# Robosapien1.net
KiCad netlist of a schematic drawn in EAGLE
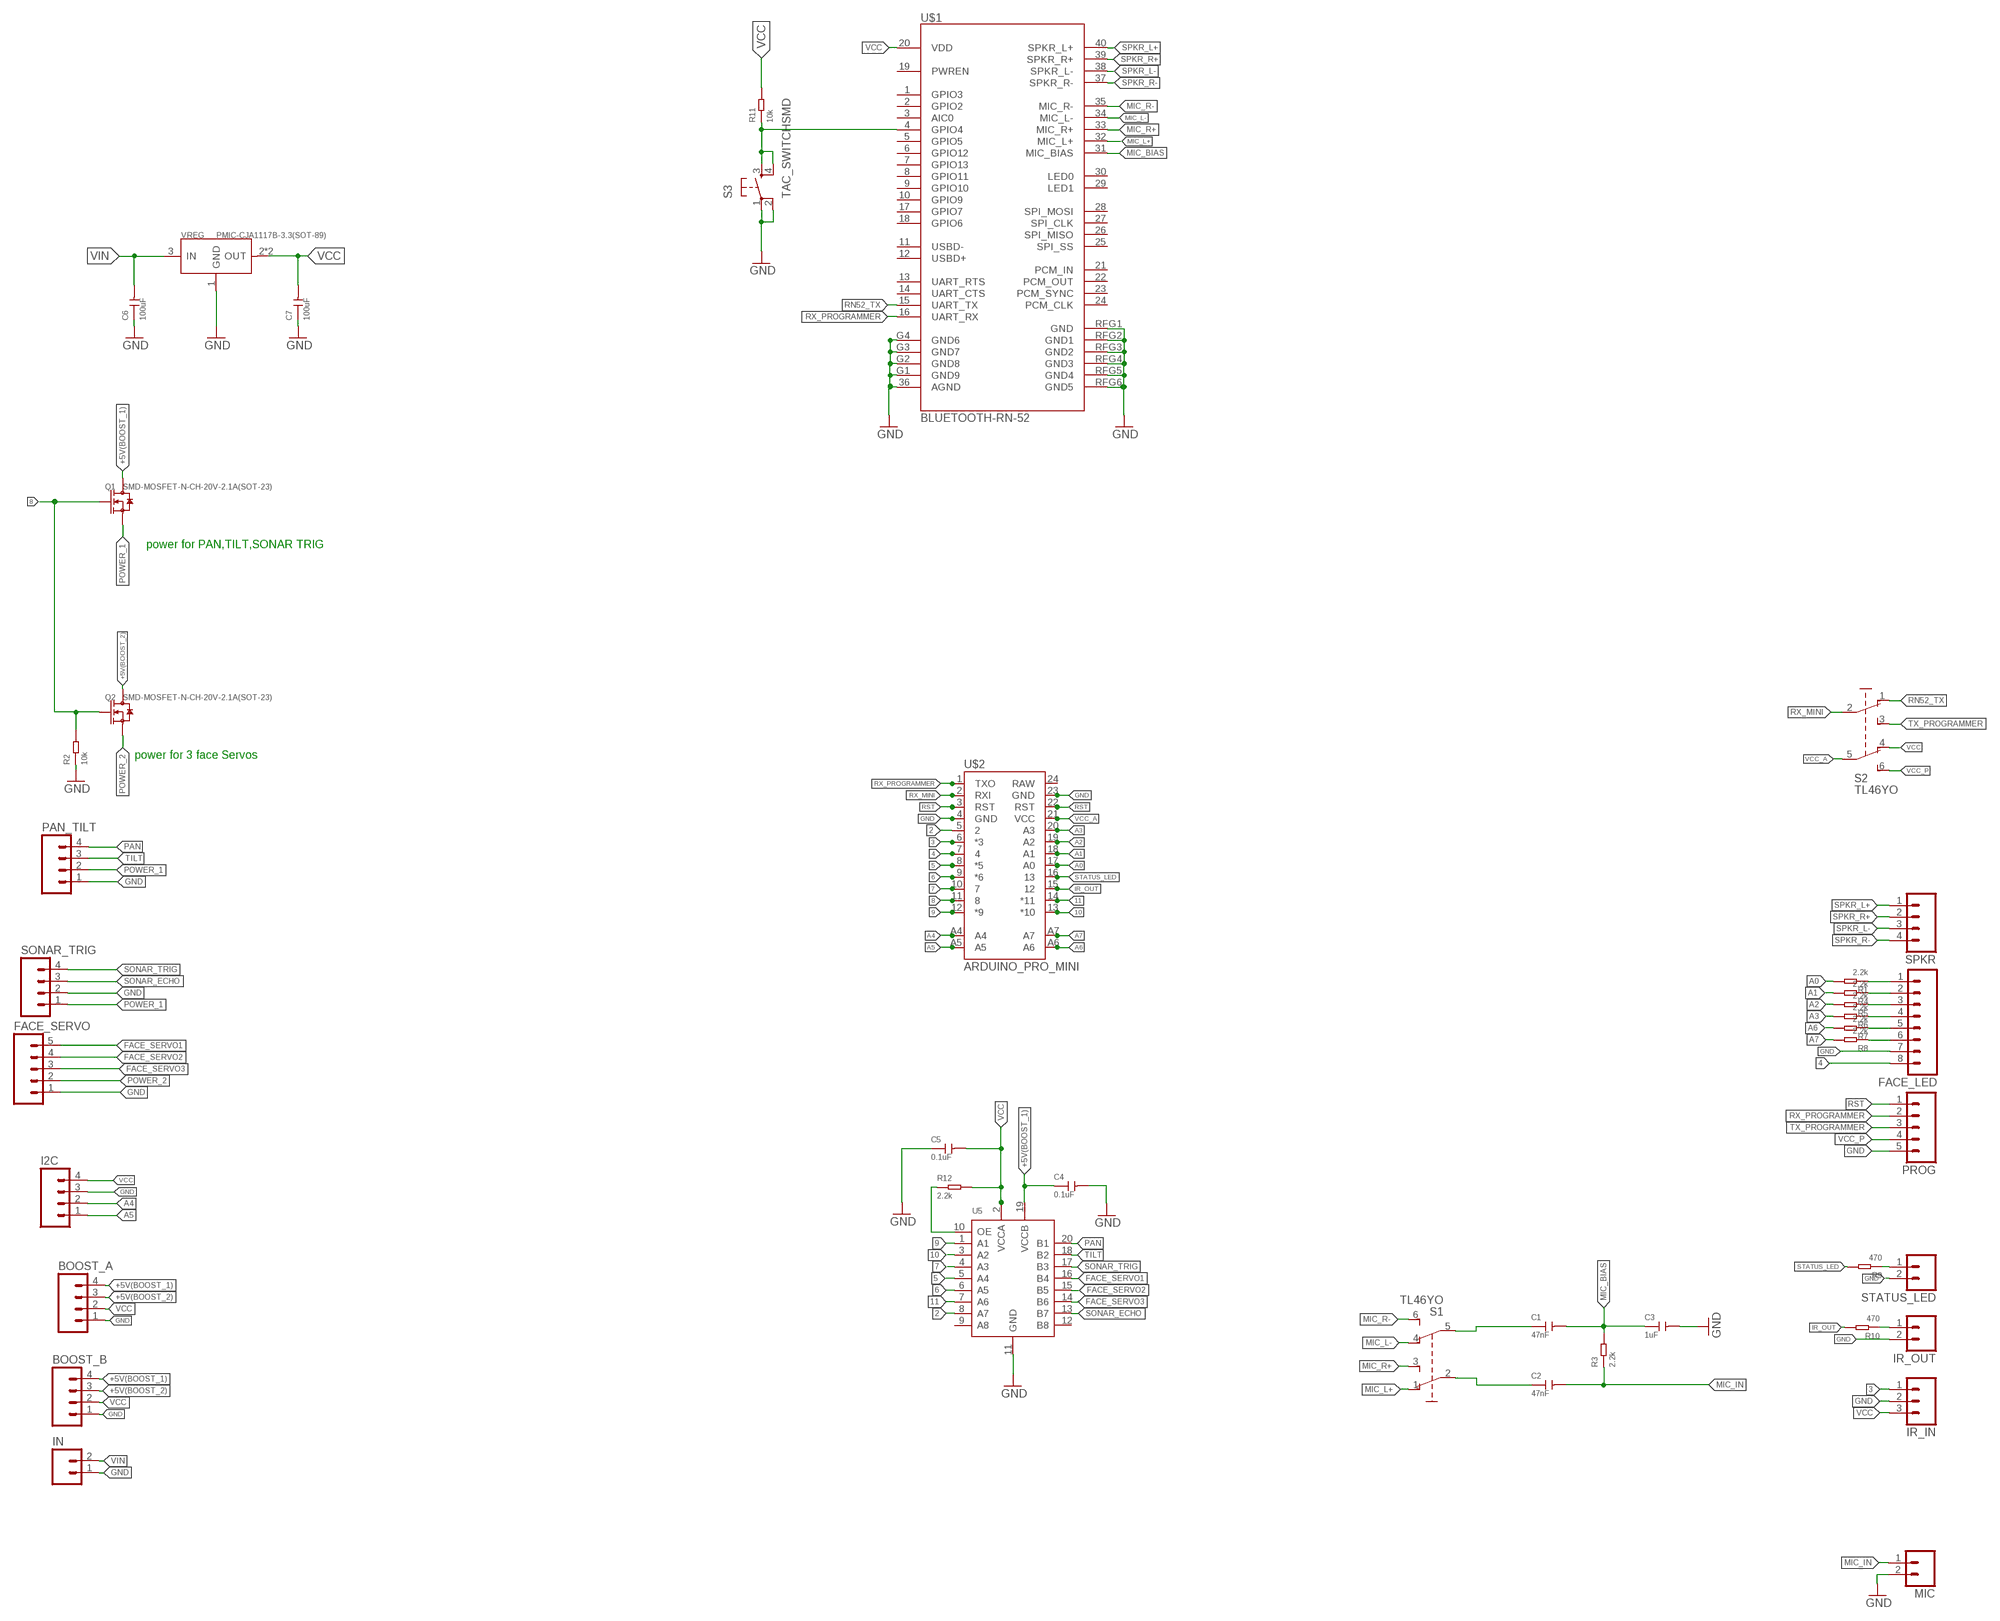
[diagram p0: schematic, sheet 1]

(export (version "E")
  (design (tool "Eeschema 10.0.6"))
  (components
    (comp (ref "BOOST_A")
      (value "M04PTH")
      (footprint "eagle-import:1X04")
      (libsource (lib "eagle-import") (part "M04PTH"))
    )
    (comp (ref "BOOST_B")
      (value "M04PTH")
      (footprint "eagle-import:1X04")
      (libsource (lib "eagle-import") (part "M04PTH"))
    )
    (comp (ref "C1")
      (value "47nF")
      (footprint "eagle-import:C0402S")
      (libsource (lib "eagle-import") (part "CAP-0402S"))
    )
    (comp (ref "C2")
      (value "47nF")
      (footprint "eagle-import:C0402S")
      (libsource (lib "eagle-import") (part "CAP-0402S"))
    )
    (comp (ref "C3")
      (value "1uF")
      (footprint "eagle-import:C0402S")
      (libsource (lib "eagle-import") (part "CAP-0402S"))
    )
    (comp (ref "C4")
      (value "0.1uF")
      (footprint "eagle-import:C0402S")
      (libsource (lib "eagle-import") (part "CAP-0402S"))
    )
    (comp (ref "C5")
      (value "0.1uF")
      (footprint "eagle-import:C0402S")
      (libsource (lib "eagle-import") (part "CAP-0402S"))
    )
    (comp (ref "C6")
      (value "100uF")
      (footprint "eagle-import:C0402S")
      (libsource (lib "eagle-import") (part "CAP-0402S"))
    )
    (comp (ref "C7")
      (value "100uF")
      (footprint "eagle-import:C0402S")
      (libsource (lib "eagle-import") (part "CAP-0402S"))
    )
    (comp (ref "FACE_LED")
      (value "M08")
      (footprint "eagle-import:1X08_ROUND")
      (libsource (lib "eagle-import") (part "M08"))
    )
    (comp (ref "FACE_SERVO")
      (value "M05PTH")
      (footprint "eagle-import:1X05")
      (libsource (lib "eagle-import") (part "M05PTH"))
    )
    (comp (ref "I2C")
      (value "M04PTH")
      (footprint "eagle-import:1X04")
      (libsource (lib "eagle-import") (part "M04PTH"))
    )
    (comp (ref "IN")
      (value "M02PTH")
      (footprint "eagle-import:1X02")
      (libsource (lib "eagle-import") (part "M02PTH"))
    )
    (comp (ref "IR_IN")
      (value "M03PTH")
      (footprint "eagle-import:1X03")
      (libsource (lib "eagle-import") (part "M03PTH"))
    )
    (comp (ref "IR_OUT")
      (value "M02PTH")
      (footprint "eagle-import:1X02")
      (libsource (lib "eagle-import") (part "M02PTH"))
    )
    (comp (ref "MIC")
      (value "M02PTH")
      (footprint "eagle-import:1X02")
      (libsource (lib "eagle-import") (part "M02PTH"))
    )
    (comp (ref "PAN_TILT")
      (value "M04PTH")
      (footprint "eagle-import:1X04")
      (libsource (lib "eagle-import") (part "M04PTH"))
    )
    (comp (ref "PROG")
      (value "M05PTH")
      (footprint "eagle-import:1X05")
      (libsource (lib "eagle-import") (part "M05PTH"))
    )
    (comp (ref "Q1")
      (value "SMD-MOSFET-N-CH-20V-2.1A(SOT-23)")
      (footprint "eagle-import:SOT-23")
      (fields (field (name "MPN") "CJ2302"))
      (libsource (lib "eagle-import") (part "SMD-MOSFET-N-CH-20V-2.1A(SOT-23)"))
    )
    (comp (ref "Q2")
      (value "SMD-MOSFET-N-CH-20V-2.1A(SOT-23)")
      (footprint "eagle-import:SOT-23")
      (fields (field (name "MPN") "CJ2302"))
      (libsource (lib "eagle-import") (part "SMD-MOSFET-N-CH-20V-2.1A(SOT-23)"))
    )
    (comp (ref "R1")
      (value "2.2k")
      (footprint "eagle-import:R0402S")
      (libsource (lib "eagle-import") (part "RES'-0402S'"))
    )
    (comp (ref "R2")
      (value "10k")
      (footprint "eagle-import:R0402S")
      (libsource (lib "eagle-import") (part "RES'-0402S'"))
    )
    (comp (ref "R3")
      (value "2.2k")
      (footprint "eagle-import:R0402S")
      (libsource (lib "eagle-import") (part "RES'-0402S'"))
    )
    (comp (ref "R4")
      (value "2.2k")
      (footprint "eagle-import:R0402S")
      (libsource (lib "eagle-import") (part "RES'-0402S'"))
    )
    (comp (ref "R5")
      (value "2.2k")
      (footprint "eagle-import:R0402S")
      (libsource (lib "eagle-import") (part "RES'-0402S'"))
    )
    (comp (ref "R6")
      (value "2.2k")
      (footprint "eagle-import:R0402S")
      (libsource (lib "eagle-import") (part "RES'-0402S'"))
    )
    (comp (ref "R7")
      (value "2.2k")
      (footprint "eagle-import:R0402S")
      (libsource (lib "eagle-import") (part "RES'-0402S'"))
    )
    (comp (ref "R8")
      (value "2.2k")
      (footprint "eagle-import:R0402S")
      (libsource (lib "eagle-import") (part "RES'-0402S'"))
    )
    (comp (ref "R9")
      (value "470")
      (footprint "eagle-import:R0402S")
      (libsource (lib "eagle-import") (part "RES'-0402S'"))
    )
    (comp (ref "R10")
      (value "470")
      (footprint "eagle-import:R0402S")
      (libsource (lib "eagle-import") (part "RES'-0402S'"))
    )
    (comp (ref "R11")
      (value "10k")
      (footprint "eagle-import:R0402S")
      (libsource (lib "eagle-import") (part "RES'-0402S'"))
    )
    (comp (ref "R12")
      (value "2.2k")
      (footprint "eagle-import:R0402S")
      (libsource (lib "eagle-import") (part "RES'-0402S'"))
    )
    (comp (ref "S1")
      (value "TL46YO")
      (footprint "eagle-import:TL4XYO")
      (libsource (lib "eagle-import") (part "TL46YO"))
    )
    (comp (ref "S2")
      (value "TL46YO")
      (footprint "eagle-import:TL4XYO")
      (libsource (lib "eagle-import") (part "TL46YO"))
    )
    (comp (ref "S3")
      (value "TAC_SWITCHSMD")
      (footprint "eagle-import:TACTILE-SWITCH-SMD")
      (libsource (lib "eagle-import") (part "TAC_SWITCHSMD"))
    )
    (comp (ref "SONAR_TRIG")
      (value "M04PTH")
      (footprint "eagle-import:1X04")
      (libsource (lib "eagle-import") (part "M04PTH"))
    )
    (comp (ref "SPKR")
      (value "M04PTH")
      (footprint "eagle-import:1X04")
      (libsource (lib "eagle-import") (part "M04PTH"))
    )
    (comp (ref "STATUS_LED")
      (value "M02PTH")
      (footprint "eagle-import:1X02")
      (libsource (lib "eagle-import") (part "M02PTH"))
    )
    (comp (ref "U$1")
      (value "BLUETOOTH-RN-52")
      (footprint "eagle-import:RN-52")
      (libsource (lib "eagle-import") (part "BLUETOOTH-RN-52"))
    )
    (comp (ref "U$2")
      (value "ARDUINO_PRO_MINI")
      (footprint "eagle-import:ARDUINO_PRO_MINI")
      (libsource (lib "eagle-import") (part "ARDUINO_PRO_MINI"))
    )
    (comp (ref "U5")
      (value "LOGIC-TXS0108EPWR(TSSOP20)")
      (footprint "eagle-import:TSSOP20-0.65-6.5X4.4MM")
      (libsource (lib "eagle-import") (part "LOGIC-TXS0108EPWR(TSSOP20)"))
    )
    (comp (ref "VREG")
      (value "PMIC-CJA1117B-3.3(SOT-89)")
      (footprint "eagle-import:SOT-89")
      (fields (field (name "MPN") "PMIC-LDO-Vin-5V-Vout-3.3V-1A"))
      (libsource (lib "eagle-import") (part "PMIC-CJA1117B-3.3(SOT-89)"))
    )
  )
  (nets
    (net (code "1") (name "+5V(BOOST_1)") (class "Default")
      (node (ref "BOOST_A") (pin "4") (pinfunction "4_4") (pintype "passive"))
      (node (ref "BOOST_B") (pin "4") (pinfunction "4_4") (pintype "passive"))
      (node (ref "C4") (pin "1") (pinfunction "1_1") (pintype "passive"))
      (node (ref "Q1") (pin "3") (pinfunction "D_3") (pintype "passive"))
      (node (ref "U5") (pin "19") (pinfunction "VCCB_19") (pintype "bidirectional"))
    )
    (net (code "2") (name "+5V(BOOST_2)") (class "Default")
      (node (ref "BOOST_A") (pin "3") (pinfunction "3_3") (pintype "passive"))
      (node (ref "BOOST_B") (pin "3") (pinfunction "3_3") (pintype "passive"))
      (node (ref "Q2") (pin "3") (pinfunction "D_3") (pintype "passive"))
    )
    (net (code "3") (name "2") (class "Default")
      (node (ref "U$2") (pin "5") (pinfunction "2_5") (pintype "bidirectional"))
      (node (ref "U5") (pin "8") (pinfunction "A7_8") (pintype "bidirectional"))
    )
    (net (code "4") (name "3") (class "Default")
      (node (ref "IR_IN") (pin "1") (pinfunction "1_1") (pintype "passive"))
      (node (ref "U$2") (pin "6") (pinfunction "*3_6") (pintype "bidirectional"))
    )
    (net (code "5") (name "4") (class "Default")
      (node (ref "FACE_LED") (pin "8") (pinfunction "8_8") (pintype "passive"))
      (node (ref "U$2") (pin "7") (pinfunction "4_7") (pintype "bidirectional"))
    )
    (net (code "6") (name "5") (class "Default")
      (node (ref "U$2") (pin "8") (pinfunction "*5_8") (pintype "bidirectional"))
      (node (ref "U5") (pin "5") (pinfunction "A4_5") (pintype "bidirectional"))
    )
    (net (code "7") (name "6") (class "Default")
      (node (ref "U$2") (pin "9") (pinfunction "*6_9") (pintype "bidirectional"))
      (node (ref "U5") (pin "6") (pinfunction "A5_6") (pintype "bidirectional"))
    )
    (net (code "8") (name "7") (class "Default")
      (node (ref "U$2") (pin "10") (pinfunction "7_10") (pintype "bidirectional"))
      (node (ref "U5") (pin "4") (pinfunction "A3_4") (pintype "bidirectional"))
    )
    (net (code "9") (name "8") (class "Default")
      (node (ref "Q1") (pin "1") (pinfunction "G_1") (pintype "passive"))
      (node (ref "Q2") (pin "1") (pinfunction "G_1") (pintype "passive"))
      (node (ref "R2") (pin "2") (pinfunction "2_2") (pintype "passive"))
      (node (ref "U$2") (pin "11") (pinfunction "8_11") (pintype "bidirectional"))
    )
    (net (code "10") (name "9") (class "Default")
      (node (ref "U$2") (pin "12") (pinfunction "*9_12") (pintype "bidirectional"))
      (node (ref "U5") (pin "1") (pinfunction "A1_1") (pintype "bidirectional"))
    )
    (net (code "11") (name "10") (class "Default")
      (node (ref "U$2") (pin "13") (pinfunction "*10_13") (pintype "bidirectional"))
      (node (ref "U5") (pin "3") (pinfunction "A2_3") (pintype "bidirectional"))
    )
    (net (code "12") (name "11") (class "Default")
      (node (ref "U$2") (pin "14") (pinfunction "*11_14") (pintype "bidirectional"))
      (node (ref "U5") (pin "7") (pinfunction "A6_7") (pintype "bidirectional"))
    )
    (net (code "13") (name "A0") (class "Default")
      (node (ref "R1") (pin "2") (pinfunction "2_2") (pintype "passive"))
      (node (ref "U$2") (pin "17") (pinfunction "A0_17") (pintype "bidirectional"))
    )
    (net (code "14") (name "A1") (class "Default")
      (node (ref "R4") (pin "2") (pinfunction "2_2") (pintype "passive"))
      (node (ref "U$2") (pin "18") (pinfunction "A1_18") (pintype "bidirectional"))
    )
    (net (code "15") (name "A2") (class "Default")
      (node (ref "R5") (pin "2") (pinfunction "2_2") (pintype "passive"))
      (node (ref "U$2") (pin "19") (pinfunction "A2_19") (pintype "bidirectional"))
    )
    (net (code "16") (name "A3") (class "Default")
      (node (ref "R6") (pin "2") (pinfunction "2_2") (pintype "passive"))
      (node (ref "U$2") (pin "20") (pinfunction "A3_20") (pintype "bidirectional"))
    )
    (net (code "17") (name "A4") (class "Default")
      (node (ref "I2C") (pin "2") (pinfunction "2_2") (pintype "passive"))
      (node (ref "U$2") (pin "A4") (pinfunction "A4_A4") (pintype "bidirectional"))
    )
    (net (code "18") (name "A5") (class "Default")
      (node (ref "I2C") (pin "1") (pinfunction "1_1") (pintype "passive"))
      (node (ref "U$2") (pin "A5") (pinfunction "A5_A5") (pintype "bidirectional"))
    )
    (net (code "19") (name "A6") (class "Default")
      (node (ref "R7") (pin "2") (pinfunction "2_2") (pintype "passive"))
      (node (ref "U$2") (pin "A6") (pinfunction "A6_A6") (pintype "bidirectional"))
    )
    (net (code "20") (name "A7") (class "Default")
      (node (ref "R8") (pin "2") (pinfunction "2_2") (pintype "passive"))
      (node (ref "U$2") (pin "A7") (pinfunction "A7_A7") (pintype "bidirectional"))
    )
    (net (code "21") (name "FACE_SERVO1") (class "Default")
      (node (ref "FACE_SERVO") (pin "5") (pinfunction "5_5") (pintype "passive"))
      (node (ref "U5") (pin "16") (pinfunction "B4_16") (pintype "bidirectional"))
    )
    (net (code "22") (name "FACE_SERVO2") (class "Default")
      (node (ref "FACE_SERVO") (pin "4") (pinfunction "4_4") (pintype "passive"))
      (node (ref "U5") (pin "15") (pinfunction "B5_15") (pintype "bidirectional"))
    )
    (net (code "23") (name "FACE_SERVO3") (class "Default")
      (node (ref "FACE_SERVO") (pin "3") (pinfunction "3_3") (pintype "passive"))
      (node (ref "U5") (pin "14") (pinfunction "B6_14") (pintype "bidirectional"))
    )
    (net (code "24") (name "GND") (class "Default")
      (node (ref "BOOST_A") (pin "1") (pinfunction "1_1") (pintype "passive"))
      (node (ref "BOOST_B") (pin "1") (pinfunction "1_1") (pintype "passive"))
      (node (ref "C3") (pin "2") (pinfunction "2_2") (pintype "passive"))
      (node (ref "C4") (pin "2") (pinfunction "2_2") (pintype "passive"))
      (node (ref "C5") (pin "1") (pinfunction "1_1") (pintype "passive"))
      (node (ref "C6") (pin "1") (pinfunction "1_1") (pintype "passive"))
      (node (ref "C7") (pin "1") (pinfunction "1_1") (pintype "passive"))
      (node (ref "FACE_LED") (pin "7") (pinfunction "7_7") (pintype "passive"))
      (node (ref "FACE_SERVO") (pin "1") (pinfunction "1_1") (pintype "passive"))
      (node (ref "I2C") (pin "3") (pinfunction "3_3") (pintype "passive"))
      (node (ref "IN") (pin "1") (pinfunction "1_1") (pintype "passive"))
      (node (ref "IR_IN") (pin "2") (pinfunction "2_2") (pintype "passive"))
      (node (ref "IR_OUT") (pin "2") (pinfunction "2_2") (pintype "passive"))
      (node (ref "MIC") (pin "2") (pinfunction "2_2") (pintype "passive"))
      (node (ref "PAN_TILT") (pin "1") (pinfunction "1_1") (pintype "passive"))
      (node (ref "PROG") (pin "5") (pinfunction "5_5") (pintype "passive"))
      (node (ref "R2") (pin "1") (pinfunction "1_1") (pintype "passive"))
      (node (ref "S3") (pin "1") (pinfunction "1_1") (pintype "passive"))
      (node (ref "S3") (pin "2") (pinfunction "2_2") (pintype "passive"))
      (node (ref "SONAR_TRIG") (pin "2") (pinfunction "2_2") (pintype "passive"))
      (node (ref "STATUS_LED") (pin "2") (pinfunction "2_2") (pintype "passive"))
      (node (ref "U$1") (pin "36") (pinfunction "AGND_36") (pintype "bidirectional"))
      (node (ref "U$1") (pin "G1") (pinfunction "GND9_G1") (pintype "bidirectional"))
      (node (ref "U$1") (pin "G2") (pinfunction "GND8_G2") (pintype "bidirectional"))
      (node (ref "U$1") (pin "G3") (pinfunction "GND7_G3") (pintype "bidirectional"))
      (node (ref "U$1") (pin "G4") (pinfunction "GND6_G4") (pintype "bidirectional"))
      (node (ref "U$1") (pin "RFG1") (pinfunction "GND_RFG1") (pintype "bidirectional"))
      (node (ref "U$1") (pin "RFG2") (pinfunction "GND1_RFG2") (pintype "bidirectional"))
      (node (ref "U$1") (pin "RFG3") (pinfunction "GND2_RFG3") (pintype "bidirectional"))
      (node (ref "U$1") (pin "RFG4") (pinfunction "GND3_RFG4") (pintype "bidirectional"))
      (node (ref "U$1") (pin "RFG5") (pinfunction "GND4_RFG5") (pintype "bidirectional"))
      (node (ref "U$1") (pin "RFG6") (pinfunction "GND5_RFG6") (pintype "bidirectional"))
      (node (ref "U$2") (pin "23") (pinfunction "GND_23") (pintype "bidirectional"))
      (node (ref "U$2") (pin "4") (pinfunction "GND_4") (pintype "bidirectional"))
      (node (ref "U5") (pin "11") (pinfunction "GND_11") (pintype "bidirectional"))
      (node (ref "VREG") (pin "1") (pinfunction "GND_1") (pintype "bidirectional"))
    )
    (net (code "25") (name "IR_OUT") (class "Default")
      (node (ref "R10") (pin "2") (pinfunction "2_2") (pintype "passive"))
      (node (ref "U$2") (pin "15") (pinfunction "12_15") (pintype "bidirectional"))
    )
    (net (code "26") (name "MIC_BIAS") (class "Default")
      (node (ref "C1") (pin "2") (pinfunction "2_2") (pintype "passive"))
      (node (ref "C3") (pin "1") (pinfunction "1_1") (pintype "passive"))
      (node (ref "R3") (pin "2") (pinfunction "2_2") (pintype "passive"))
      (node (ref "U$1") (pin "31") (pinfunction "MIC_BIAS_31") (pintype "bidirectional"))
    )
    (net (code "27") (name "MIC_IN") (class "Default")
      (node (ref "C2") (pin "2") (pinfunction "2_2") (pintype "passive"))
      (node (ref "MIC") (pin "1") (pinfunction "1_1") (pintype "passive"))
      (node (ref "R3") (pin "1") (pinfunction "1_1") (pintype "passive"))
    )
    (net (code "28") (name "MIC_L+") (class "Default")
      (node (ref "S1") (pin "1") (pinfunction "O_1") (pintype "passive"))
      (node (ref "U$1") (pin "32") (pinfunction "MIC_L+_32") (pintype "bidirectional"))
    )
    (net (code "29") (name "MIC_L-") (class "Default")
      (node (ref "S1") (pin "4") (pinfunction "O1_4") (pintype "passive"))
      (node (ref "U$1") (pin "34") (pinfunction "MIC_L-_34") (pintype "bidirectional"))
    )
    (net (code "30") (name "MIC_R+") (class "Default")
      (node (ref "S1") (pin "3") (pinfunction "S_3") (pintype "passive"))
      (node (ref "U$1") (pin "33") (pinfunction "MIC_R+_33") (pintype "bidirectional"))
    )
    (net (code "31") (name "MIC_R-") (class "Default")
      (node (ref "S1") (pin "6") (pinfunction "S1_6") (pintype "passive"))
      (node (ref "U$1") (pin "35") (pinfunction "MIC_R-_35") (pintype "bidirectional"))
    )
    (net (code "32") (name "Net-(FACE_LED-Pad1)") (class "Default")
      (node (ref "FACE_LED") (pin "1") (pinfunction "1_1") (pintype "passive"))
      (node (ref "R1") (pin "1") (pinfunction "1_1") (pintype "passive"))
    )
    (net (code "33") (name "Net-(FACE_LED-Pad2)") (class "Default")
      (node (ref "FACE_LED") (pin "2") (pinfunction "2_2") (pintype "passive"))
      (node (ref "R4") (pin "1") (pinfunction "1_1") (pintype "passive"))
    )
    (net (code "34") (name "Net-(FACE_LED-Pad3)") (class "Default")
      (node (ref "FACE_LED") (pin "3") (pinfunction "3_3") (pintype "passive"))
      (node (ref "R5") (pin "1") (pinfunction "1_1") (pintype "passive"))
    )
    (net (code "35") (name "Net-(FACE_LED-Pad4)") (class "Default")
      (node (ref "FACE_LED") (pin "4") (pinfunction "4_4") (pintype "passive"))
      (node (ref "R6") (pin "1") (pinfunction "1_1") (pintype "passive"))
    )
    (net (code "36") (name "Net-(FACE_LED-Pad5)") (class "Default")
      (node (ref "FACE_LED") (pin "5") (pinfunction "5_5") (pintype "passive"))
      (node (ref "R7") (pin "1") (pinfunction "1_1") (pintype "passive"))
    )
    (net (code "37") (name "Net-(FACE_LED-Pad6)") (class "Default")
      (node (ref "FACE_LED") (pin "6") (pinfunction "6_6") (pintype "passive"))
      (node (ref "R8") (pin "1") (pinfunction "1_1") (pintype "passive"))
    )
    (net (code "38") (name "Net-(IR_OUT-Pad1)") (class "Default")
      (node (ref "IR_OUT") (pin "1") (pinfunction "1_1") (pintype "passive"))
      (node (ref "R10") (pin "1") (pinfunction "1_1") (pintype "passive"))
    )
    (net (code "39") (name "Net-(R9-Pad1)") (class "Default")
      (node (ref "R9") (pin "1") (pinfunction "1_1") (pintype "passive"))
      (node (ref "STATUS_LED") (pin "1") (pinfunction "1_1") (pintype "passive"))
    )
    (net (code "40") (name "Net-(S1-P)") (class "Default")
      (node (ref "C2") (pin "1") (pinfunction "1_1") (pintype "passive"))
      (node (ref "S1") (pin "2") (pinfunction "P_2") (pintype "passive"))
    )
    (net (code "41") (name "Net-(S1-P1)") (class "Default")
      (node (ref "C1") (pin "1") (pinfunction "1_1") (pintype "passive"))
      (node (ref "S1") (pin "5") (pinfunction "P1_5") (pintype "passive"))
    )
    (net (code "42") (name "Net-(U$1-GPIO4)") (class "Default")
      (node (ref "R11") (pin "1") (pinfunction "1_1") (pintype "passive"))
      (node (ref "S3") (pin "3") (pinfunction "3_3") (pintype "passive"))
      (node (ref "S3") (pin "4") (pinfunction "4_4") (pintype "passive"))
      (node (ref "U$1") (pin "4") (pinfunction "GPIO4_4") (pintype "bidirectional"))
    )
    (net (code "43") (name "Net-(U5-OE)") (class "Default")
      (node (ref "R12") (pin "1") (pinfunction "1_1") (pintype "passive"))
      (node (ref "U5") (pin "10") (pinfunction "OE_10") (pintype "bidirectional"))
    )
    (net (code "44") (name "PAN") (class "Default")
      (node (ref "PAN_TILT") (pin "4") (pinfunction "4_4") (pintype "passive"))
      (node (ref "U5") (pin "20") (pinfunction "B1_20") (pintype "bidirectional"))
    )
    (net (code "45") (name "POWER_1") (class "Default")
      (node (ref "PAN_TILT") (pin "2") (pinfunction "2_2") (pintype "passive"))
      (node (ref "Q1") (pin "2") (pinfunction "S_2") (pintype "passive"))
      (node (ref "SONAR_TRIG") (pin "1") (pinfunction "1_1") (pintype "passive"))
    )
    (net (code "46") (name "POWER_2") (class "Default")
      (node (ref "FACE_SERVO") (pin "2") (pinfunction "2_2") (pintype "passive"))
      (node (ref "Q2") (pin "2") (pinfunction "S_2") (pintype "passive"))
    )
    (net (code "47") (name "RN52_TX") (class "Default")
      (node (ref "S2") (pin "1") (pinfunction "O_1") (pintype "passive"))
      (node (ref "U$1") (pin "15") (pinfunction "UART_TX_15") (pintype "bidirectional"))
    )
    (net (code "48") (name "RST") (class "Default")
      (node (ref "PROG") (pin "1") (pinfunction "1_1") (pintype "passive"))
      (node (ref "U$2") (pin "22") (pinfunction "RST_22") (pintype "bidirectional"))
      (node (ref "U$2") (pin "3") (pinfunction "RST_3") (pintype "bidirectional"))
    )
    (net (code "49") (name "RX_MINI") (class "Default")
      (node (ref "S2") (pin "2") (pinfunction "P_2") (pintype "passive"))
      (node (ref "U$2") (pin "2") (pinfunction "RXI_2") (pintype "bidirectional"))
    )
    (net (code "50") (name "RX_PROGRAMMER") (class "Default")
      (node (ref "PROG") (pin "2") (pinfunction "2_2") (pintype "passive"))
      (node (ref "U$1") (pin "16") (pinfunction "UART_RX_16") (pintype "bidirectional"))
      (node (ref "U$2") (pin "1") (pinfunction "TXO_1") (pintype "bidirectional"))
    )
    (net (code "51") (name "SONAR_ECHO") (class "Default")
      (node (ref "SONAR_TRIG") (pin "3") (pinfunction "3_3") (pintype "passive"))
      (node (ref "U5") (pin "13") (pinfunction "B7_13") (pintype "bidirectional"))
    )
    (net (code "52") (name "SONAR_TRIG") (class "Default")
      (node (ref "SONAR_TRIG") (pin "4") (pinfunction "4_4") (pintype "passive"))
      (node (ref "U5") (pin "17") (pinfunction "B3_17") (pintype "bidirectional"))
    )
    (net (code "53") (name "SPKR_L+") (class "Default")
      (node (ref "SPKR") (pin "1") (pinfunction "1_1") (pintype "passive"))
      (node (ref "U$1") (pin "40") (pinfunction "SPKR_L+_40") (pintype "bidirectional"))
    )
    (net (code "54") (name "SPKR_L-") (class "Default")
      (node (ref "SPKR") (pin "3") (pinfunction "3_3") (pintype "passive"))
      (node (ref "U$1") (pin "38") (pinfunction "SPKR_L-_38") (pintype "bidirectional"))
    )
    (net (code "55") (name "SPKR_R+") (class "Default")
      (node (ref "SPKR") (pin "2") (pinfunction "2_2") (pintype "passive"))
      (node (ref "U$1") (pin "39") (pinfunction "SPKR_R+_39") (pintype "bidirectional"))
    )
    (net (code "56") (name "SPKR_R-") (class "Default")
      (node (ref "SPKR") (pin "4") (pinfunction "4_4") (pintype "passive"))
      (node (ref "U$1") (pin "37") (pinfunction "SPKR_R-_37") (pintype "bidirectional"))
    )
    (net (code "57") (name "STATUS_LED") (class "Default")
      (node (ref "R9") (pin "2") (pinfunction "2_2") (pintype "passive"))
      (node (ref "U$2") (pin "16") (pinfunction "13_16") (pintype "bidirectional"))
    )
    (net (code "58") (name "TILT") (class "Default")
      (node (ref "PAN_TILT") (pin "3") (pinfunction "3_3") (pintype "passive"))
      (node (ref "U5") (pin "18") (pinfunction "B2_18") (pintype "bidirectional"))
    )
    (net (code "59") (name "TX_PROGRAMMER") (class "Default")
      (node (ref "PROG") (pin "3") (pinfunction "3_3") (pintype "passive"))
      (node (ref "S2") (pin "3") (pinfunction "S_3") (pintype "passive"))
    )
    (net (code "60") (name "VCC") (class "Default")
      (node (ref "BOOST_A") (pin "2") (pinfunction "2_2") (pintype "passive"))
      (node (ref "BOOST_B") (pin "2") (pinfunction "2_2") (pintype "passive"))
      (node (ref "C5") (pin "2") (pinfunction "2_2") (pintype "passive"))
      (node (ref "C7") (pin "2") (pinfunction "2_2") (pintype "passive"))
      (node (ref "I2C") (pin "4") (pinfunction "4_4") (pintype "passive"))
      (node (ref "IR_IN") (pin "3") (pinfunction "3_3") (pintype "passive"))
      (node (ref "R11") (pin "2") (pinfunction "2_2") (pintype "passive"))
      (node (ref "R12") (pin "2") (pinfunction "2_2") (pintype "passive"))
      (node (ref "S2") (pin "4") (pinfunction "O1_4") (pintype "passive"))
      (node (ref "U$1") (pin "20") (pinfunction "VDD_20") (pintype "bidirectional"))
      (node (ref "U5") (pin "2") (pinfunction "VCCA_2") (pintype "bidirectional"))
      (node (ref "VREG") (pin "2") (pinfunction "OUT_2") (pintype "bidirectional"))
      (node (ref "VREG") (pin "4") (pinfunction "OUT_4") (pintype "bidirectional"))
    )
    (net (code "61") (name "VCC_A") (class "Default")
      (node (ref "S2") (pin "5") (pinfunction "P1_5") (pintype "passive"))
      (node (ref "U$2") (pin "21") (pinfunction "VCC_21") (pintype "bidirectional"))
    )
    (net (code "62") (name "VCC_P") (class "Default")
      (node (ref "PROG") (pin "4") (pinfunction "4_4") (pintype "passive"))
      (node (ref "S2") (pin "6") (pinfunction "S1_6") (pintype "passive"))
    )
    (net (code "63") (name "VIN") (class "Default")
      (node (ref "C6") (pin "2") (pinfunction "2_2") (pintype "passive"))
      (node (ref "IN") (pin "2") (pinfunction "2_2") (pintype "passive"))
      (node (ref "VREG") (pin "3") (pinfunction "IN_3") (pintype "bidirectional"))
    )
    (net (code "64") (name "unconnected-(U$1-AIC0-Pad3)") (class "Default")
      (node (ref "U$1") (pin "3") (pinfunction "AIC0_3") (pintype "bidirectional"))
    )
    (net (code "65") (name "unconnected-(U$1-GPIO2-Pad2)") (class "Default")
      (node (ref "U$1") (pin "2") (pinfunction "GPIO2_2") (pintype "bidirectional"))
    )
    (net (code "66") (name "unconnected-(U$1-GPIO3-Pad1)") (class "Default")
      (node (ref "U$1") (pin "1") (pinfunction "GPIO3_1") (pintype "bidirectional"))
    )
    (net (code "67") (name "unconnected-(U$1-GPIO5-Pad5)") (class "Default")
      (node (ref "U$1") (pin "5") (pinfunction "GPIO5_5") (pintype "bidirectional"))
    )
    (net (code "68") (name "unconnected-(U$1-GPIO6-Pad18)") (class "Default")
      (node (ref "U$1") (pin "18") (pinfunction "GPIO6_18") (pintype "bidirectional"))
    )
    (net (code "69") (name "unconnected-(U$1-GPIO7-Pad17)") (class "Default")
      (node (ref "U$1") (pin "17") (pinfunction "GPIO7_17") (pintype "bidirectional"))
    )
    (net (code "70") (name "unconnected-(U$1-GPIO9-Pad10)") (class "Default")
      (node (ref "U$1") (pin "10") (pinfunction "GPIO9_10") (pintype "bidirectional"))
    )
    (net (code "71") (name "unconnected-(U$1-GPIO10-Pad9)") (class "Default")
      (node (ref "U$1") (pin "9") (pinfunction "GPIO10_9") (pintype "bidirectional"))
    )
    (net (code "72") (name "unconnected-(U$1-GPIO11-Pad8)") (class "Default")
      (node (ref "U$1") (pin "8") (pinfunction "GPIO11_8") (pintype "bidirectional"))
    )
    (net (code "73") (name "unconnected-(U$1-GPIO12-Pad6)") (class "Default")
      (node (ref "U$1") (pin "6") (pinfunction "GPIO12_6") (pintype "bidirectional"))
    )
    (net (code "74") (name "unconnected-(U$1-GPIO13-Pad7)") (class "Default")
      (node (ref "U$1") (pin "7") (pinfunction "GPIO13_7") (pintype "bidirectional"))
    )
    (net (code "75") (name "unconnected-(U$1-LED0-Pad30)") (class "Default")
      (node (ref "U$1") (pin "30") (pinfunction "LED0_30") (pintype "bidirectional"))
    )
    (net (code "76") (name "unconnected-(U$1-LED1-Pad29)") (class "Default")
      (node (ref "U$1") (pin "29") (pinfunction "LED1_29") (pintype "bidirectional"))
    )
    (net (code "77") (name "unconnected-(U$1-PCM_CLK-Pad24)") (class "Default")
      (node (ref "U$1") (pin "24") (pinfunction "PCM_CLK_24") (pintype "bidirectional"))
    )
    (net (code "78") (name "unconnected-(U$1-PCM_IN-Pad21)") (class "Default")
      (node (ref "U$1") (pin "21") (pinfunction "PCM_IN_21") (pintype "bidirectional"))
    )
    (net (code "79") (name "unconnected-(U$1-PCM_OUT-Pad22)") (class "Default")
      (node (ref "U$1") (pin "22") (pinfunction "PCM_OUT_22") (pintype "bidirectional"))
    )
    (net (code "80") (name "unconnected-(U$1-PCM_SYNC-Pad23)") (class "Default")
      (node (ref "U$1") (pin "23") (pinfunction "PCM_SYNC_23") (pintype "bidirectional"))
    )
    (net (code "81") (name "unconnected-(U$1-PWREN-Pad19)") (class "Default")
      (node (ref "U$1") (pin "19") (pinfunction "PWREN_19") (pintype "bidirectional"))
    )
    (net (code "82") (name "unconnected-(U$1-SPI_CLK-Pad27)") (class "Default")
      (node (ref "U$1") (pin "27") (pinfunction "SPI_CLK_27") (pintype "bidirectional"))
    )
    (net (code "83") (name "unconnected-(U$1-SPI_MISO-Pad26)") (class "Default")
      (node (ref "U$1") (pin "26") (pinfunction "SPI_MISO_26") (pintype "bidirectional"))
    )
    (net (code "84") (name "unconnected-(U$1-SPI_MOSI-Pad28)") (class "Default")
      (node (ref "U$1") (pin "28") (pinfunction "SPI_MOSI_28") (pintype "bidirectional"))
    )
    (net (code "85") (name "unconnected-(U$1-SPI_SS-Pad25)") (class "Default")
      (node (ref "U$1") (pin "25") (pinfunction "SPI_SS_25") (pintype "bidirectional"))
    )
    (net (code "86") (name "unconnected-(U$1-UART_CTS-Pad14)") (class "Default")
      (node (ref "U$1") (pin "14") (pinfunction "UART_CTS_14") (pintype "bidirectional"))
    )
    (net (code "87") (name "unconnected-(U$1-UART_RTS-Pad13)") (class "Default")
      (node (ref "U$1") (pin "13") (pinfunction "UART_RTS_13") (pintype "bidirectional"))
    )
    (net (code "88") (name "unconnected-(U$1-USBD+-Pad12)") (class "Default")
      (node (ref "U$1") (pin "12") (pinfunction "USBD+_12") (pintype "bidirectional"))
    )
    (net (code "89") (name "unconnected-(U$1-USBD--Pad11)") (class "Default")
      (node (ref "U$1") (pin "11") (pinfunction "USBD-_11") (pintype "bidirectional"))
    )
    (net (code "90") (name "unconnected-(U$2-RAW-Pad24)") (class "Default")
      (node (ref "U$2") (pin "24") (pinfunction "RAW_24") (pintype "bidirectional"))
    )
    (net (code "91") (name "unconnected-(U5-A8-Pad9)") (class "Default")
      (node (ref "U5") (pin "9") (pinfunction "A8_9") (pintype "bidirectional"))
    )
    (net (code "92") (name "unconnected-(U5-B8-Pad12)") (class "Default")
      (node (ref "U5") (pin "12") (pinfunction "B8_12") (pintype "bidirectional"))
    )
  )
)
